# PushButtonRed.net
KiCad netlist of a schematic drawn in Altium Designer
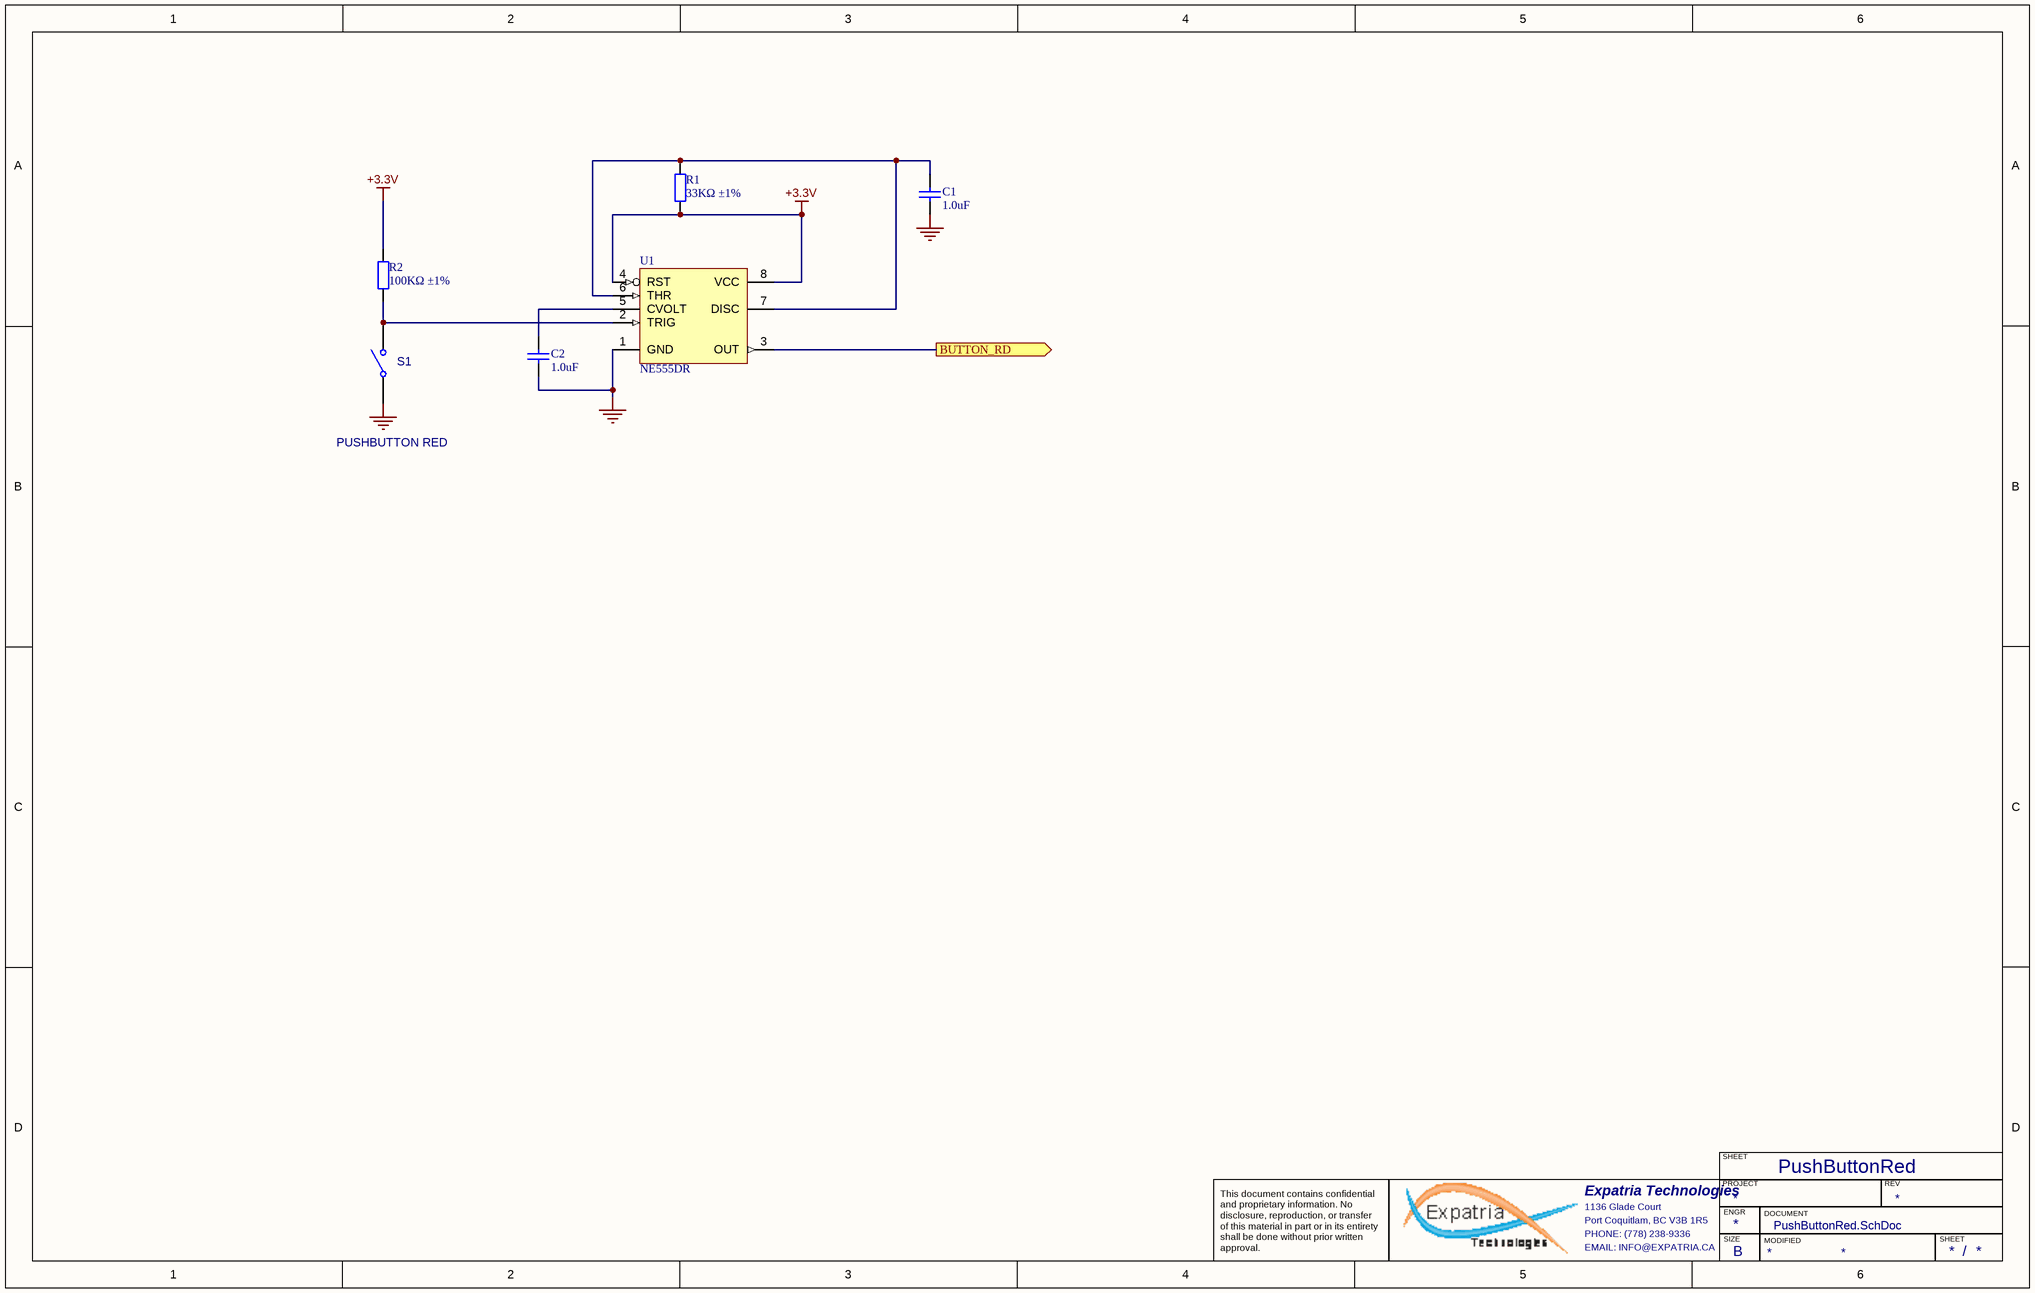
[diagram p0: PushButtonRed.SchDoc]

(export (version "E")
  (design (tool "Eeschema 10.0.6"))
  (components
    (comp (ref "C1")
      (value "1.0uF")
      (footprint "0402_C")
      (description "Chip capacitor")
      (fields
        (field (name "MANUFACTURER") "Samsung Electro-Mechanics")
        (field (name "PARTNUMBER") "CL05A105KA5NQNC")
      )
      (libsource (lib "Cap") (part "0402 1.0uF (105) 10% 25V"))
    )
    (comp (ref "C2")
      (value "1.0uF")
      (footprint "0402_C")
      (description "Chip capacitor")
      (fields
        (field (name "MANUFACTURER") "Samsung Electro-Mechanics")
        (field (name "PARTNUMBER") "CL05A105KA5NQNC")
      )
      (libsource (lib "Cap") (part "0402 1.0uF (105) 10% 25V"))
    )
    (comp (ref "R1")
      (value "33KΩ ±1%")
      (footprint "0402_R")
      (description "Chip resistor")
      (fields (field (name "MANUFACTURER") "Uniroyal Elec") (field (name "PARTNUMBER") "0402WGF3302TCE"))
      (libsource (lib "RES") (part "0402 33K (3302) 1%"))
    )
    (comp (ref "R2")
      (value "100KΩ ±1%")
      (footprint "0402_R")
      (description "Chip resistor")
      (fields (field (name "MANUFACTURER") "Uniroyal Elec") (field (name "PARTNUMBER") "0402WGF1003TCE"))
      (libsource (lib "RES") (part "0402 100K (1003) 1%"))
    )
    (comp (ref "S1")
      (value "PUSHBUTTON RED")
      (footprint "D6C10F1LFS_RED")
      (description "SWITCH PUSH SPST-NO 0.1A 32V RED")
      (libsource (lib "bluebell") (part "D6R40 F1 LFS"))
    )
    (comp (ref "U1")
      (value "NE555DR")
      (footprint "SOIC-8_150mil")
      (description "时基集成")
      (libsource (lib "IC") (part "NE555DR_[C7593]"))
    )
  )
  (nets
    (net (code "1") (name "+3.3V") (class "Default")
      (node (ref "R1") (pin "1") (pinfunction "1_1") (pintype "passive"))
      (node (ref "R2") (pin "2") (pinfunction "2_2") (pintype "passive"))
      (node (ref "U1") (pin "4") (pinfunction "RST_4") (pintype "input"))
      (node (ref "U1") (pin "8") (pinfunction "VCC_8") (pintype "power_in"))
    )
    (net (code "2") (name "/BUTTON_RD") (class "Default")
      (node (ref "U1") (pin "3") (pinfunction "OUT_3") (pintype "output"))
    )
    (net (code "3") (name "GND") (class "Default")
      (node (ref "C1") (pin "1") (pinfunction "1_1") (pintype "passive"))
      (node (ref "C2") (pin "2") (pinfunction "2_2") (pintype "passive"))
      (node (ref "S1") (pin "1") (pinfunction "COMMON_1") (pintype "passive"))
      (node (ref "U1") (pin "1") (pinfunction "GND_1") (pintype "power_in"))
    )
    (net (code "4") (name "Net-(S1-NO)") (class "Default")
      (node (ref "R2") (pin "1") (pinfunction "1_1") (pintype "passive"))
      (node (ref "S1") (pin "2") (pinfunction "NO_2") (pintype "passive"))
      (node (ref "U1") (pin "2") (pinfunction "TRIG_2") (pintype "input"))
    )
    (net (code "5") (name "Net-(U1-CVOLT)") (class "Default")
      (node (ref "C2") (pin "1") (pinfunction "1_1") (pintype "passive"))
      (node (ref "U1") (pin "5") (pinfunction "CVOLT_5") (pintype "passive"))
    )
    (net (code "6") (name "Net-(U1-DISC)") (class "Default")
      (node (ref "C1") (pin "2") (pinfunction "2_2") (pintype "passive"))
      (node (ref "R1") (pin "2") (pinfunction "2_2") (pintype "passive"))
      (node (ref "U1") (pin "6") (pinfunction "THR_6") (pintype "input"))
      (node (ref "U1") (pin "7") (pinfunction "DISC_7") (pintype "open_collector"))
    )
  )
)
